# stepup.net
KiCad netlist of a schematic drawn in EAGLE
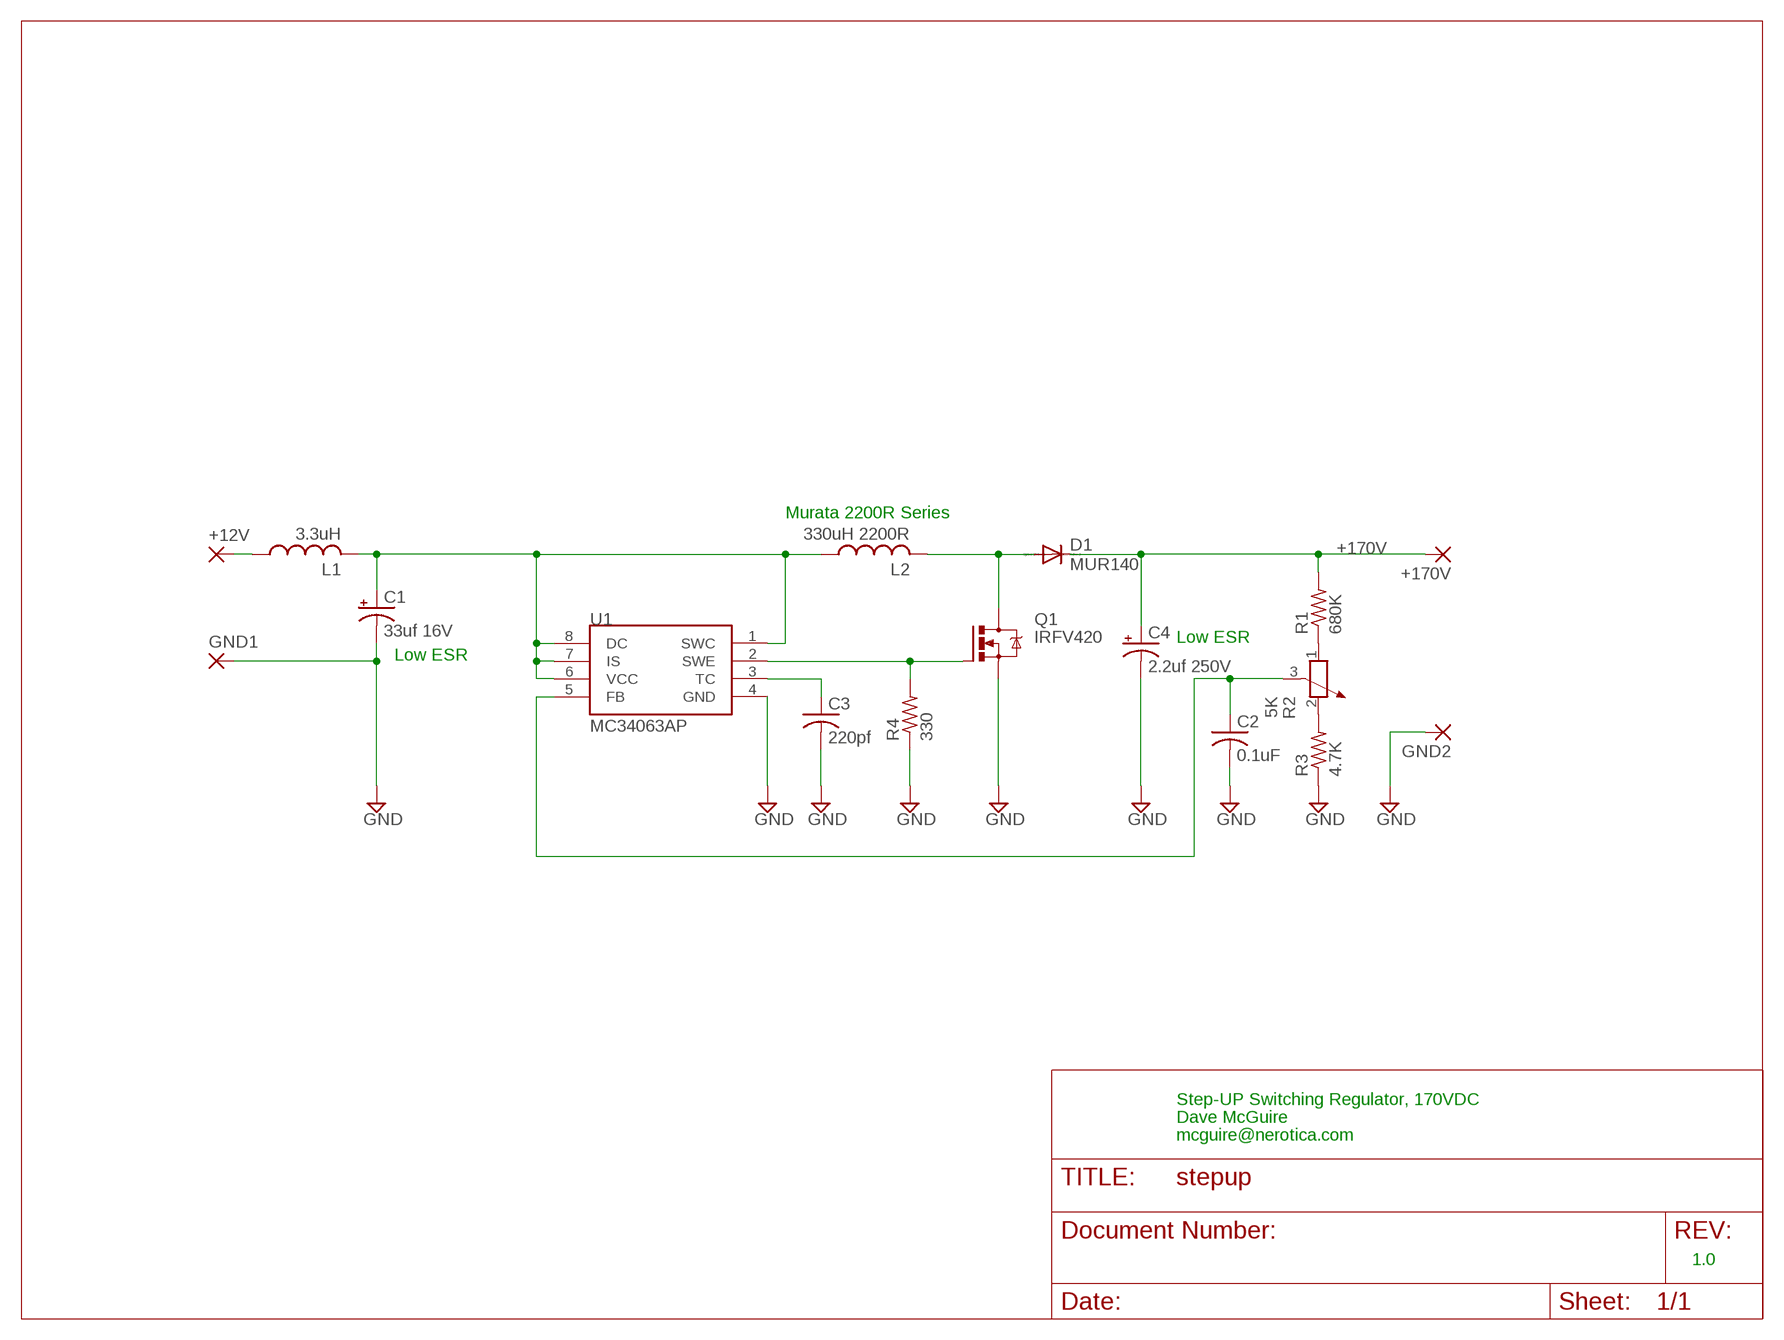
[diagram p0: schematic, sheet 1]

(export (version "E")
  (design (tool "Eeschema 10.0.6"))
  (components
    (comp (ref "+12V")
      (value "2,54/0,9")
      (footprint "eagle-import:2,54_0,9")
      (libsource (lib "eagle-import") (part "2,54/0,9"))
    )
    (comp (ref "+170V")
      (value "2,54/0,9")
      (footprint "eagle-import:2,54_0,9")
      (libsource (lib "eagle-import") (part "2,54/0,9"))
    )
    (comp (ref "C1")
      (value "33uf 16V")
      (footprint "eagle-import:E2,5-6E")
      (libsource (lib "eagle-import") (part "CPOL-USE2,5-6E"))
    )
    (comp (ref "C2")
      (value "0.1uF")
      (footprint "eagle-import:C050-025X075")
      (libsource (lib "eagle-import") (part "C-US050-025X075"))
    )
    (comp (ref "C3")
      (value "220pf")
      (footprint "eagle-import:C050-025X075")
      (libsource (lib "eagle-import") (part "C-US050-025X075"))
    )
    (comp (ref "C4")
      (value "2.2uf 250V")
      (footprint "eagle-import:E2,5-6E")
      (libsource (lib "eagle-import") (part "CPOL-USE2,5-6E"))
    )
    (comp (ref "D1")
      (value "MUR140")
      (footprint "eagle-import:DO41-10")
      (libsource (lib "eagle-import") (part "MUR150RL"))
    )
    (comp (ref "GND1")
      (value "2,54/0,9")
      (footprint "eagle-import:2,54_0,9")
      (libsource (lib "eagle-import") (part "2,54/0,9"))
    )
    (comp (ref "GND2")
      (value "2,54/0,9")
      (footprint "eagle-import:2,54_0,9")
      (libsource (lib "eagle-import") (part "2,54/0,9"))
    )
    (comp (ref "L1")
      (value "3.3uH")
      (footprint "eagle-import:0207_10")
      (libsource (lib "eagle-import") (part "L-US0207/10"))
    )
    (comp (ref "L2")
      (value "330uH 2200R")
      (footprint "eagle-import:0207_10")
      (libsource (lib "eagle-import") (part "L-US0207/10"))
    )
    (comp (ref "Q1")
      (value "IRFV420")
      (footprint "eagle-import:TO220BV")
      (libsource (lib "eagle-import") (part "IRF740"))
    )
    (comp (ref "R1")
      (value "680K")
      (footprint "eagle-import:0207_10")
      (libsource (lib "eagle-import") (part "R-US_0207/10"))
    )
    (comp (ref "R2")
      (value "5K")
      (footprint "eagle-import:PT-10S")
      (libsource (lib "eagle-import") (part "POTENTIOMETER_PT-10S"))
    )
    (comp (ref "R3")
      (value "4.7K")
      (footprint "eagle-import:0207_10")
      (libsource (lib "eagle-import") (part "R-US_0207/10"))
    )
    (comp (ref "R4")
      (value "330")
      (footprint "eagle-import:0207_10")
      (libsource (lib "eagle-import") (part "R-US_0207/10"))
    )
    (comp (ref "U1")
      (value "MC34063AP")
      (footprint "eagle-import:DIL08")
      (libsource (lib "eagle-import") (part "MC34063AP"))
    )
  )
  (nets
    (net (code "1") (name "/+170V") (class "Default")
      (node (ref "+170V") (pin "1") (pinfunction "P_1") (pintype "passive"))
      (node (ref "C4") (pin "+") (pinfunction "+_+") (pintype "passive"))
      (node (ref "D1") (pin "C") (pinfunction "C_C") (pintype "passive"))
      (node (ref "R1") (pin "2") (pinfunction "2_2") (pintype "passive"))
    )
    (net (code "2") (name "GND") (class "Default")
      (node (ref "C1") (pin "-") (pinfunction "-_-") (pintype "passive"))
      (node (ref "C2") (pin "2") (pinfunction "2_2") (pintype "passive"))
      (node (ref "C3") (pin "2") (pinfunction "2_2") (pintype "passive"))
      (node (ref "C4") (pin "-") (pinfunction "-_-") (pintype "passive"))
      (node (ref "GND1") (pin "1") (pinfunction "P_1") (pintype "passive"))
      (node (ref "GND2") (pin "1") (pinfunction "P_1") (pintype "passive"))
      (node (ref "Q1") (pin "S") (pinfunction "S_S") (pintype "passive"))
      (node (ref "R3") (pin "1") (pinfunction "1_1") (pintype "passive"))
      (node (ref "R4") (pin "1") (pinfunction "1_1") (pintype "passive"))
      (node (ref "U1") (pin "4") (pinfunction "GND_4") (pintype "passive"))
    )
    (net (code "3") (name "Net-(+12V-P)") (class "Default")
      (node (ref "+12V") (pin "1") (pinfunction "P_1") (pintype "passive"))
      (node (ref "L1") (pin "1") (pinfunction "1_1") (pintype "passive"))
    )
    (net (code "4") (name "Net-(D1-PadA)") (class "Default")
      (node (ref "D1") (pin "A") (pinfunction "A_A") (pintype "passive"))
      (node (ref "L2") (pin "2") (pinfunction "2_2") (pintype "passive"))
      (node (ref "Q1") (pin "D") (pinfunction "D_D") (pintype "passive"))
    )
    (net (code "5") (name "Net-(R1-Pad1)") (class "Default")
      (node (ref "R1") (pin "1") (pinfunction "1_1") (pintype "passive"))
      (node (ref "R2") (pin "1") (pinfunction "1_1") (pintype "passive"))
    )
    (net (code "6") (name "Net-(R2-Pad2)") (class "Default")
      (node (ref "R2") (pin "2") (pinfunction "2_2") (pintype "passive"))
      (node (ref "R3") (pin "2") (pinfunction "2_2") (pintype "passive"))
    )
    (net (code "7") (name "Net-(U1-DC)") (class "Default")
      (node (ref "C1") (pin "+") (pinfunction "+_+") (pintype "passive"))
      (node (ref "L1") (pin "2") (pinfunction "2_2") (pintype "passive"))
      (node (ref "L2") (pin "1") (pinfunction "1_1") (pintype "passive"))
      (node (ref "U1") (pin "1") (pinfunction "SWC_1") (pintype "passive"))
      (node (ref "U1") (pin "6") (pinfunction "VCC_6") (pintype "passive"))
      (node (ref "U1") (pin "7") (pinfunction "IS_7") (pintype "passive"))
      (node (ref "U1") (pin "8") (pinfunction "DC_8") (pintype "passive"))
    )
    (net (code "8") (name "Net-(U1-FB)") (class "Default")
      (node (ref "C2") (pin "1") (pinfunction "1_1") (pintype "passive"))
      (node (ref "R2") (pin "3") (pinfunction "3_3") (pintype "passive"))
      (node (ref "U1") (pin "5") (pinfunction "FB_5") (pintype "passive"))
    )
    (net (code "9") (name "Net-(U1-SWE)") (class "Default")
      (node (ref "Q1") (pin "G") (pinfunction "G_G") (pintype "passive"))
      (node (ref "R4") (pin "2") (pinfunction "2_2") (pintype "passive"))
      (node (ref "U1") (pin "2") (pinfunction "SWE_2") (pintype "passive"))
    )
    (net (code "10") (name "Net-(U1-TC)") (class "Default")
      (node (ref "C3") (pin "1") (pinfunction "1_1") (pintype "passive"))
      (node (ref "U1") (pin "3") (pinfunction "TC_3") (pintype "passive"))
    )
  )
)
